# Beefy_3.net
KiCad netlist of a schematic drawn in EAGLE
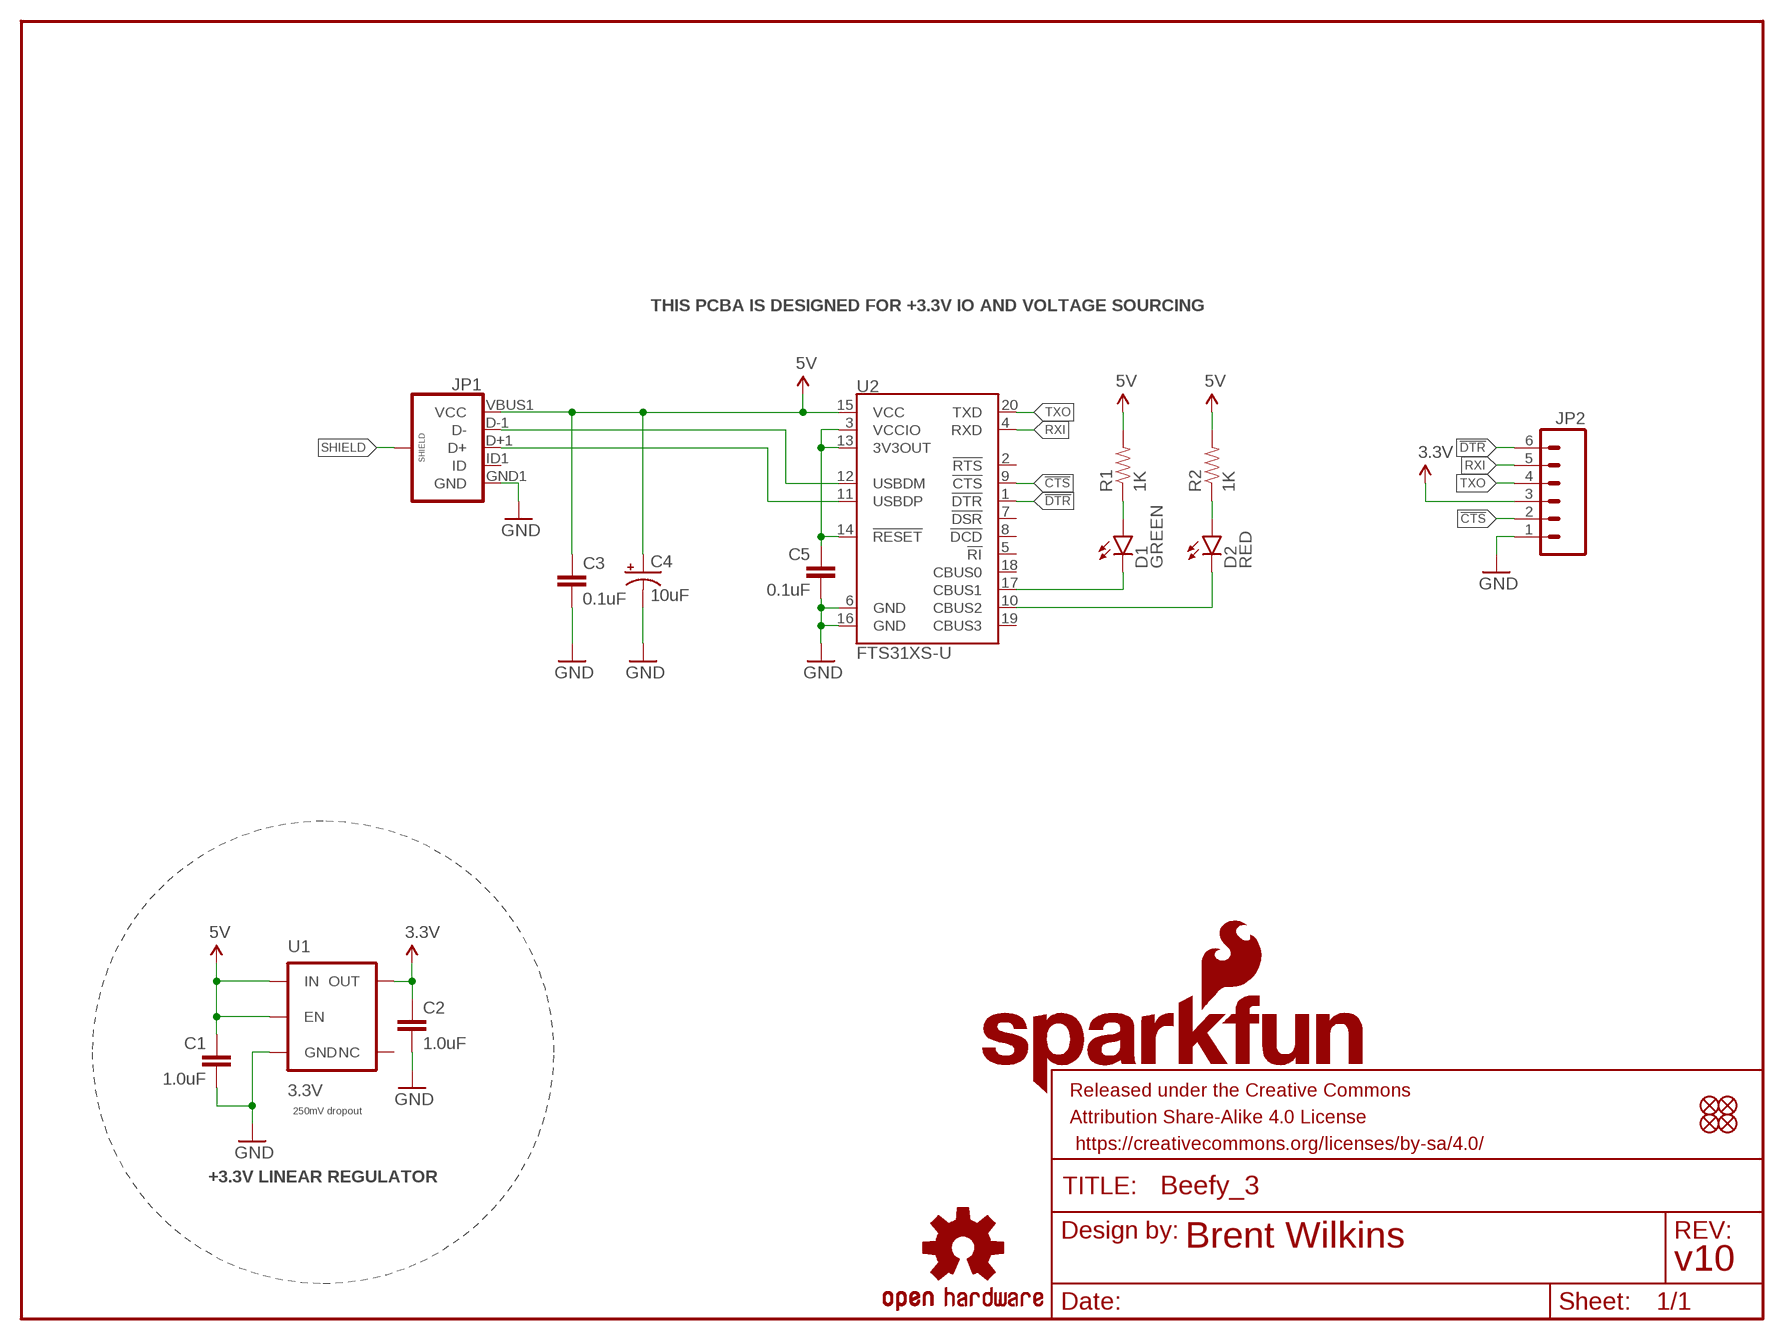
[diagram p0: schematic, sheet 1]

(export (version "E")
  (design (tool "Eeschema 10.0.6"))
  (components
    (comp (ref "C1")
      (value "1.0uF")
      (footprint "eagle-import:0603-CAP")
      (libsource (lib "eagle-import") (part "1.0UF-16V-10%(0603)"))
    )
    (comp (ref "C2")
      (value "1.0uF")
      (footprint "eagle-import:0603-CAP")
      (libsource (lib "eagle-import") (part "1.0UF-16V-10%(0603)"))
    )
    (comp (ref "C3")
      (value "0.1uF")
      (footprint "eagle-import:0603-CAP")
      (libsource (lib "eagle-import") (part "0.1UF-25V(+80/-20%)(0603)"))
    )
    (comp (ref "C4")
      (value "10uF")
      (footprint "eagle-import:EIA3216")
      (libsource (lib "eagle-import") (part "10UF-16V-10%(TANT)"))
    )
    (comp (ref "C5")
      (value "0.1uF")
      (footprint "eagle-import:0603-CAP")
      (libsource (lib "eagle-import") (part "0.1UF-25V(+80/-20%)(0603)"))
    )
    (comp (ref "D1")
      (value "GREEN")
      (footprint "eagle-import:LED-0603")
      (libsource (lib "eagle-import") (part "LED-GREEN0603"))
    )
    (comp (ref "D2")
      (value "RED")
      (footprint "eagle-import:LED-0603")
      (libsource (lib "eagle-import") (part "LED-RED0603"))
    )
    (comp (ref "FRAME1")
      (value "FRAME-LETTER")
      (footprint "eagle-import:CREATIVE_COMMONS")
      (libsource (lib "eagle-import") (part "FRAME-LETTER"))
    )
    (comp (ref "JP1")
      (value "USB_MICROB_PLUGCONN-11752")
      (footprint "eagle-import:USB-B-MICRO-SMD_V03")
      (libsource (lib "eagle-import") (part "USB_MICROB_PLUGCONN-11752"))
    )
    (comp (ref "JP2")
      (value "M06SMD-FEMALE-V2")
      (footprint "eagle-import:1X06-SMD-FEMALE-V2")
      (libsource (lib "eagle-import") (part "M06SMD-FEMALE-V2"))
    )
    (comp (ref "JP3")
      (value "FIDUCIAL1X2")
      (footprint "eagle-import:FIDUCIAL-1X2")
      (libsource (lib "eagle-import") (part "FIDUCIAL1X2"))
    )
    (comp (ref "JP4")
      (value "FIDUCIAL1X2")
      (footprint "eagle-import:FIDUCIAL-1X2")
      (libsource (lib "eagle-import") (part "FIDUCIAL1X2"))
    )
    (comp (ref "JP5")
      (value "FIDUCIAL1X2")
      (footprint "eagle-import:FIDUCIAL-1X2")
      (libsource (lib "eagle-import") (part "FIDUCIAL1X2"))
    )
    (comp (ref "JP6")
      (value "FIDUCIAL1X2")
      (footprint "eagle-import:FIDUCIAL-1X2")
      (libsource (lib "eagle-import") (part "FIDUCIAL1X2"))
    )
    (comp (ref "LOGO1")
      (value "OSHW-LOGOS")
      (footprint "eagle-import:OSHW-LOGO-S")
      (libsource (lib "eagle-import") (part "OSHW-LOGOS"))
    )
    (comp (ref "LOGO2")
      (value "SFE_LOGO_NAME.1_INCH")
      (footprint "eagle-import:SFE_LOGO_NAME_.1")
      (libsource (lib "eagle-import") (part "SFE_LOGO_NAME.1_INCH"))
    )
    (comp (ref "LOGO3")
      (value "SFE_LOGO_FLAME.1_INCH")
      (footprint "eagle-import:SFE_LOGO_FLAME_.1")
      (libsource (lib "eagle-import") (part "SFE_LOGO_FLAME.1_INCH"))
    )
    (comp (ref "R1")
      (value "1K")
      (footprint "eagle-import:0603-RES")
      (libsource (lib "eagle-import") (part "1KOHM-1/10W-1%(0603)"))
    )
    (comp (ref "R2")
      (value "1K")
      (footprint "eagle-import:0603-RES")
      (libsource (lib "eagle-import") (part "1KOHM-1/10W-1%(0603)"))
    )
    (comp (ref "U1")
      (value "3.3V")
      (footprint "eagle-import:SOT23-5")
      (libsource (lib "eagle-import") (part "V_REG_AP2112K-3.3V"))
    )
    (comp (ref "U2")
      (value "FTS31XS-U")
      (footprint "eagle-import:SSOP20_L")
      (libsource (lib "eagle-import") (part "FT231XS"))
    )
  )
  (nets
    (net (code "1") (name "/~{CTS}") (class "Default")
      (node (ref "JP2") (pin "2") (pinfunction "2_2") (pintype "passive"))
      (node (ref "U2") (pin "9") (pinfunction "~{CTS}_9") (pintype "bidirectional"))
    )
    (net (code "2") (name "/~{DTR}") (class "Default")
      (node (ref "JP2") (pin "6") (pinfunction "6_6") (pintype "passive"))
      (node (ref "U2") (pin "1") (pinfunction "~{DTR}_1") (pintype "bidirectional"))
    )
    (net (code "3") (name "3.3V") (class "Default")
      (node (ref "C2") (pin "1") (pinfunction "1_1") (pintype "passive"))
      (node (ref "JP2") (pin "3") (pinfunction "3_3") (pintype "passive"))
      (node (ref "U1") (pin "5") (pinfunction "OUT_5") (pintype "passive"))
    )
    (net (code "4") (name "5V") (class "Default")
      (node (ref "C1") (pin "1") (pinfunction "1_1") (pintype "passive"))
      (node (ref "C3") (pin "1") (pinfunction "1_1") (pintype "passive"))
      (node (ref "C4") (pin "A") (pinfunction "+_A") (pintype "passive"))
      (node (ref "JP1") (pin "VBUS1") (pinfunction "VCC_VBUS1") (pintype "bidirectional"))
      (node (ref "R1") (pin "2") (pinfunction "2_2") (pintype "passive"))
      (node (ref "R2") (pin "2") (pinfunction "2_2") (pintype "passive"))
      (node (ref "U1") (pin "1") (pinfunction "IN_1") (pintype "input"))
      (node (ref "U1") (pin "3") (pinfunction "EN_3") (pintype "input"))
      (node (ref "U2") (pin "15") (pinfunction "VCC_15") (pintype "bidirectional"))
    )
    (net (code "5") (name "GND") (class "Default")
      (node (ref "C1") (pin "2") (pinfunction "2_2") (pintype "passive"))
      (node (ref "C2") (pin "2") (pinfunction "2_2") (pintype "passive"))
      (node (ref "C3") (pin "2") (pinfunction "2_2") (pintype "passive"))
      (node (ref "C4") (pin "C") (pinfunction "-_C") (pintype "passive"))
      (node (ref "C5") (pin "2") (pinfunction "2_2") (pintype "passive"))
      (node (ref "JP1") (pin "GND1") (pinfunction "GND_GND1") (pintype "bidirectional"))
      (node (ref "JP2") (pin "1") (pinfunction "1_1") (pintype "passive"))
      (node (ref "U1") (pin "2") (pinfunction "GND_2") (pintype "input"))
      (node (ref "U2") (pin "16") (pinfunction "GND_16") (pintype "bidirectional"))
      (node (ref "U2") (pin "6") (pinfunction "GND_6") (pintype "bidirectional"))
    )
    (net (code "6") (name "Net-(D1-PadA)") (class "Default")
      (node (ref "D1") (pin "A") (pinfunction "A_A") (pintype "passive"))
      (node (ref "R1") (pin "1") (pinfunction "1_1") (pintype "passive"))
    )
    (net (code "7") (name "Net-(D2-PadA)") (class "Default")
      (node (ref "D2") (pin "A") (pinfunction "A_A") (pintype "passive"))
      (node (ref "R2") (pin "1") (pinfunction "1_1") (pintype "passive"))
    )
    (net (code "8") (name "Net-(JP1-D+)") (class "Default")
      (node (ref "JP1") (pin "D+1") (pinfunction "D+_D+1") (pintype "bidirectional"))
      (node (ref "U2") (pin "11") (pinfunction "USBDP_11") (pintype "bidirectional"))
    )
    (net (code "9") (name "Net-(JP1-D-)") (class "Default")
      (node (ref "JP1") (pin "D-1") (pinfunction "D-_D-1") (pintype "bidirectional"))
      (node (ref "U2") (pin "12") (pinfunction "USBDM_12") (pintype "bidirectional"))
    )
    (net (code "10") (name "Net-(U2-3V3OUT)") (class "Default")
      (node (ref "C5") (pin "1") (pinfunction "1_1") (pintype "passive"))
      (node (ref "U2") (pin "13") (pinfunction "3V3OUT_13") (pintype "bidirectional"))
      (node (ref "U2") (pin "14") (pinfunction "~{RESET}_14") (pintype "bidirectional"))
      (node (ref "U2") (pin "3") (pinfunction "VCCIO_3") (pintype "bidirectional"))
    )
    (net (code "11") (name "Net-(U2-CBUS1)") (class "Default")
      (node (ref "D1") (pin "C") (pinfunction "C_C") (pintype "passive"))
      (node (ref "U2") (pin "17") (pinfunction "CBUS1_17") (pintype "bidirectional"))
    )
    (net (code "12") (name "Net-(U2-CBUS2)") (class "Default")
      (node (ref "D2") (pin "C") (pinfunction "C_C") (pintype "passive"))
      (node (ref "U2") (pin "10") (pinfunction "CBUS2_10") (pintype "bidirectional"))
    )
    (net (code "13") (name "RXI") (class "Default")
      (node (ref "JP2") (pin "5") (pinfunction "5_5") (pintype "passive"))
      (node (ref "U2") (pin "4") (pinfunction "RXD_4") (pintype "bidirectional"))
    )
    (net (code "14") (name "SHIELD") (class "Default")
      (node (ref "JP1") (pin "SHIELD1") (pinfunction "SHIELD_SHIELD1") (pintype "bidirectional"))
      (node (ref "JP1") (pin "SHIELD2") (pinfunction "SHIELD_SHIELD2") (pintype "bidirectional"))
      (node (ref "JP1") (pin "SHIELD3") (pinfunction "SHIELD_SHIELD3") (pintype "bidirectional"))
    )
    (net (code "15") (name "TXO") (class "Default")
      (node (ref "JP2") (pin "4") (pinfunction "4_4") (pintype "passive"))
      (node (ref "U2") (pin "20") (pinfunction "TXD_20") (pintype "bidirectional"))
    )
    (net (code "16") (name "unconnected-(JP1-ID-PadID1)") (class "Default")
      (node (ref "JP1") (pin "ID1") (pinfunction "ID_ID1") (pintype "bidirectional"))
    )
    (net (code "17") (name "unconnected-(U1-NC-Pad4)") (class "Default")
      (node (ref "U1") (pin "4") (pinfunction "NC_4") (pintype "input"))
    )
    (net (code "18") (name "unconnected-(U2-CBUS0-Pad18)") (class "Default")
      (node (ref "U2") (pin "18") (pinfunction "CBUS0_18") (pintype "bidirectional"))
    )
    (net (code "19") (name "unconnected-(U2-CBUS3-Pad19)") (class "Default")
      (node (ref "U2") (pin "19") (pinfunction "CBUS3_19") (pintype "bidirectional"))
    )
    (net (code "20") (name "unconnected-(U2-~{DCD}-Pad8)") (class "Default")
      (node (ref "U2") (pin "8") (pinfunction "~{DCD}_8") (pintype "bidirectional"))
    )
    (net (code "21") (name "unconnected-(U2-~{DSR}-Pad7)") (class "Default")
      (node (ref "U2") (pin "7") (pinfunction "~{DSR}_7") (pintype "bidirectional"))
    )
    (net (code "22") (name "unconnected-(U2-~{RI}-Pad5)") (class "Default")
      (node (ref "U2") (pin "5") (pinfunction "~{RI}_5") (pintype "bidirectional"))
    )
    (net (code "23") (name "unconnected-(U2-~{RTS}-Pad2)") (class "Default")
      (node (ref "U2") (pin "2") (pinfunction "~{RTS}_2") (pintype "bidirectional"))
    )
  )
)
